# mux_chip_test_mk2.net
KiCad netlist of a schematic drawn in EAGLE
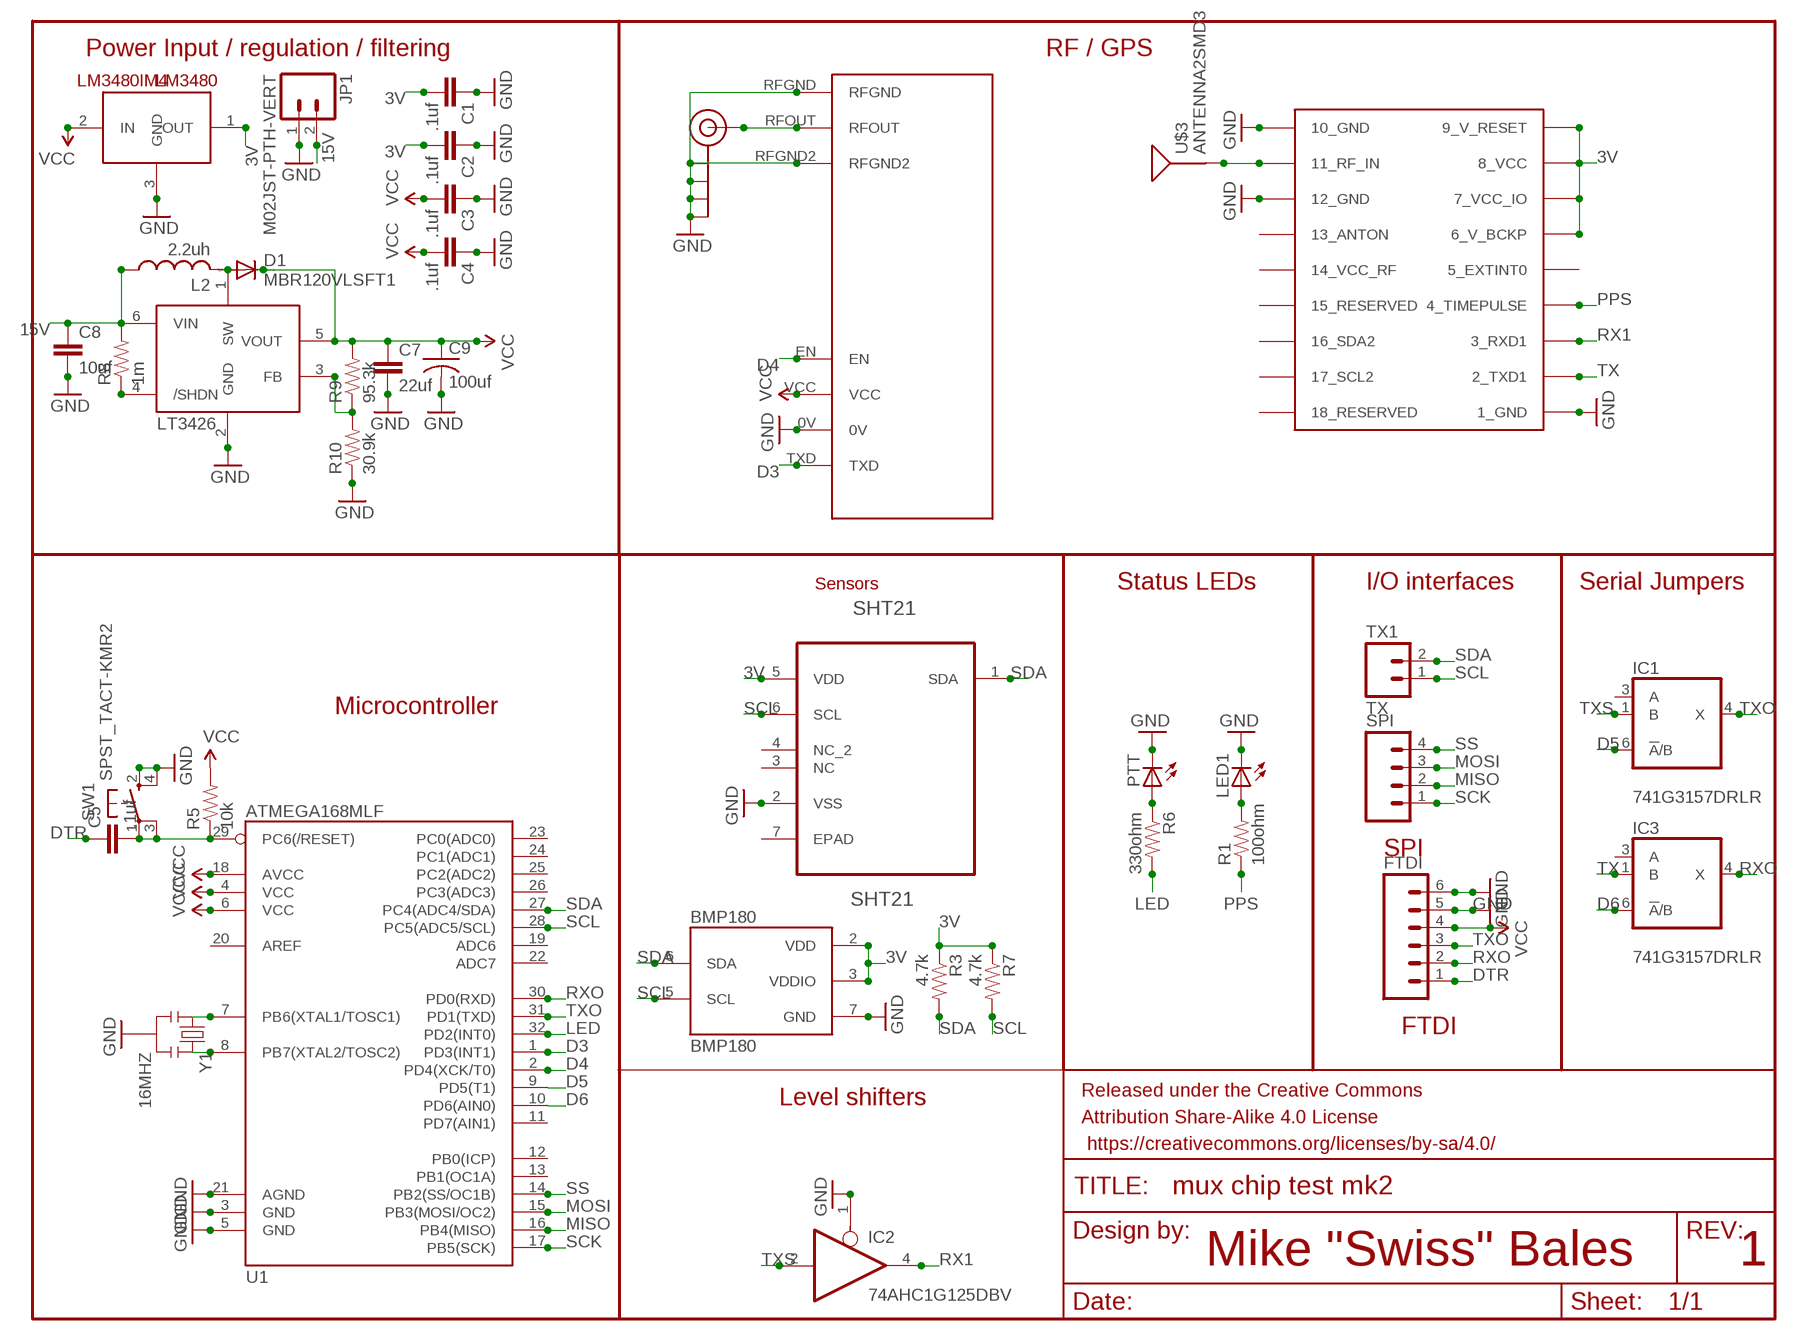
[diagram p0: schematic, sheet 1]

(export (version "E")
  (design (tool "Eeschema 10.0.6"))
  (components
    (comp (ref "BMP180")
      (value "BMP180")
      (footprint "eagle-import:BMP180")
      (libsource (lib "eagle-import") (part "BMP180"))
    )
    (comp (ref "C1")
      (value ".1uf")
      (footprint "eagle-import:0805")
      (libsource (lib "eagle-import") (part "CAP0805"))
    )
    (comp (ref "C2")
      (value ".1uf")
      (footprint "eagle-import:0805")
      (libsource (lib "eagle-import") (part "CAP0805"))
    )
    (comp (ref "C3")
      (value ".1uf")
      (footprint "eagle-import:0805")
      (libsource (lib "eagle-import") (part "CAP0805"))
    )
    (comp (ref "C4")
      (value ".1uf")
      (footprint "eagle-import:0805")
      (libsource (lib "eagle-import") (part "CAP0805"))
    )
    (comp (ref "C5")
      (value ".1uf")
      (footprint "eagle-import:0805")
      (libsource (lib "eagle-import") (part "CAP0805"))
    )
    (comp (ref "C7")
      (value "22uf")
      (footprint "eagle-import:0805")
      (libsource (lib "eagle-import") (part "CAP0805"))
    )
    (comp (ref "C8")
      (value "10uf")
      (footprint "eagle-import:0805")
      (libsource (lib "eagle-import") (part "CAP0805"))
    )
    (comp (ref "C9")
      (value "100uf")
      (footprint "eagle-import:C1206")
      (libsource (lib "eagle-import") (part "C-USC1206"))
    )
    (comp (ref "D1")
      (value "MBR120VLSFT1")
      (footprint "eagle-import:SOD123")
      (libsource (lib "eagle-import") (part "DIODE-SOD123"))
    )
    (comp (ref "FRAME1")
      (value "FRAME-LETTER")
      (footprint "eagle-import:CREATIVE_COMMONS")
      (libsource (lib "eagle-import") (part "FRAME-LETTER"))
    )
    (comp (ref "FTDI")
      (value "M06NO_SILK_FEMALE_PTH")
      (footprint "eagle-import:1X06_NO_SILK")
      (libsource (lib "eagle-import") (part "M06NO_SILK_FEMALE_PTH"))
    )
    (comp (ref "IC1")
      (value "741G3157DRLR")
      (footprint "eagle-import:DRL_R-PDSO-N6")
      (libsource (lib "eagle-import") (part "741G3157DRLR"))
    )
    (comp (ref "IC2")
      (value "74AHC1G125DBV")
      (footprint "eagle-import:SOT23-5")
      (libsource (lib "eagle-import") (part "741G125DBVAHC"))
    )
    (comp (ref "IC3")
      (value "741G3157DRLR")
      (footprint "eagle-import:DRL_R-PDSO-N6")
      (libsource (lib "eagle-import") (part "741G3157DRLR"))
    )
    (comp (ref "J$1")
      (value "SMA_EDGE")
      (footprint "eagle-import:SMA-EDGE")
      (libsource (lib "eagle-import") (part "SMA_EDGE"))
    )
    (comp (ref "JP1")
      (value "M02JST-PTH-VERT")
      (footprint "eagle-import:JST-2-PTH-VERT")
      (libsource (lib "eagle-import") (part "M02JST-PTH-VERT"))
    )
    (comp (ref "L2")
      (value "2.2uh")
      (footprint "eagle-import:L1812")
      (libsource (lib "eagle-import") (part "L-USL1812"))
    )
    (comp (ref "LED1")
      (value "LEDCHIP-LED0805")
      (footprint "eagle-import:CHIP-LED0805")
      (libsource (lib "eagle-import") (part "LEDCHIP-LED0805"))
    )
    (comp (ref "LM3480")
      (value "LM3480IM4")
      (footprint "eagle-import:SOT23-3")
      (libsource (lib "eagle-import") (part "LM3480IM4"))
    )
    (comp (ref "LT3426")
      (value "LT3426")
      (footprint "eagle-import:SOT23-6")
      (libsource (lib "eagle-import") (part "LT3426"))
    )
    (comp (ref "PTT")
      (value "LEDCHIP-LED0805")
      (footprint "eagle-import:CHIP-LED0805")
      (libsource (lib "eagle-import") (part "LEDCHIP-LED0805"))
    )
    (comp (ref "R1")
      (value "100ohm")
      (footprint "eagle-import:0805")
      (libsource (lib "eagle-import") (part "RESISTOR0805-RES"))
    )
    (comp (ref "R3")
      (value "4.7k")
      (footprint "eagle-import:0805")
      (libsource (lib "eagle-import") (part "RESISTOR0805-RES"))
    )
    (comp (ref "R5")
      (value "10k")
      (footprint "eagle-import:0805")
      (libsource (lib "eagle-import") (part "RESISTOR0805-RES"))
    )
    (comp (ref "R6")
      (value "330ohm")
      (footprint "eagle-import:0805")
      (libsource (lib "eagle-import") (part "RESISTOR0805-RES"))
    )
    (comp (ref "R7")
      (value "4.7k")
      (footprint "eagle-import:0805")
      (libsource (lib "eagle-import") (part "RESISTOR0805-RES"))
    )
    (comp (ref "R8")
      (value "1m")
      (footprint "eagle-import:0805")
      (libsource (lib "eagle-import") (part "RESISTOR0805-RES"))
    )
    (comp (ref "R9")
      (value "95.3k")
      (footprint "eagle-import:0805")
      (libsource (lib "eagle-import") (part "RESISTOR0805-RES"))
    )
    (comp (ref "R10")
      (value "30.9k")
      (footprint "eagle-import:0805")
      (libsource (lib "eagle-import") (part "RESISTOR0805-RES"))
    )
    (comp (ref "SHT21")
      (value "SHT21")
      (footprint "eagle-import:DFN300X300X110-7N")
      (libsource (lib "eagle-import") (part "SHT21"))
    )
    (comp (ref "SPI")
      (value "M04JST-PTH-VERT")
      (footprint "eagle-import:JST-4-PTH-VERT")
      (libsource (lib "eagle-import") (part "M04JST-PTH-VERT"))
    )
    (comp (ref "SW1")
      (value "SPST_TACT-KMR2")
      (footprint "eagle-import:KMR2")
      (libsource (lib "eagle-import") (part "SPST_TACT-KMR2"))
    )
    (comp (ref "TX1")
      (value "TX")
      (footprint "eagle-import:JST-2-PTH-VERT")
      (libsource (lib "eagle-import") (part "M02JST-PTH-VERT"))
    )
    (comp (ref "U$1")
      (value "UBLOX_MAX")
      (footprint "eagle-import:UBLOX_MAX")
      (libsource (lib "eagle-import") (part "UBLOX_MAX"))
    )
    (comp (ref "U$2")
      (value "RADIOMETRIX-HX1")
      (footprint "eagle-import:RADIOMETRIX-HX1")
      (libsource (lib "eagle-import") (part "RADIOMETRIX-HX1"))
    )
    (comp (ref "U$3")
      (value "ANTENNA2SMD3")
      (footprint "eagle-import:ANTENNA-CHIP4")
      (libsource (lib "eagle-import") (part "ANTENNA2SMD3"))
    )
    (comp (ref "U1")
      (value "ATMEGA168MLF")
      (footprint "eagle-import:MLF32")
      (libsource (lib "eagle-import") (part "ATMEGA168MLF"))
    )
    (comp (ref "Y1")
      (value "16MHZ")
      (footprint "eagle-import:RESONATOR-SMD")
      (libsource (lib "eagle-import") (part "RESONATOR16MHZ"))
    )
  )
  (nets
    (net (code "1") (name "/3V") (class "Default")
      (node (ref "BMP180") (pin "2") (pinfunction "VDD_2") (pintype "power_in"))
      (node (ref "BMP180") (pin "3") (pinfunction "VDDIO_3") (pintype "power_in"))
      (node (ref "C1") (pin "2") (pinfunction "2_2") (pintype "passive"))
      (node (ref "C2") (pin "2") (pinfunction "2_2") (pintype "passive"))
      (node (ref "LM3480") (pin "1") (pinfunction "OUT_1") (pintype "bidirectional"))
      (node (ref "R3") (pin "1") (pinfunction "1_1") (pintype "passive"))
      (node (ref "R7") (pin "1") (pinfunction "1_1") (pintype "passive"))
      (node (ref "SHT21") (pin "5") (pinfunction "VDD_5") (pintype "power_in"))
      (node (ref "U$1") (pin "6_V_BCKP") (pinfunction "6_V_BCKP_6_V_BCKP") (pintype "bidirectional"))
      (node (ref "U$1") (pin "7_VCC_IO") (pinfunction "7_VCC_IO_7_VCC_IO") (pintype "power_in"))
      (node (ref "U$1") (pin "8_VCC") (pinfunction "8_VCC_8_VCC") (pintype "power_in"))
      (node (ref "U$1") (pin "9_V_RESET") (pinfunction "9_V_RESET_9_V_RESET") (pintype "power_in"))
    )
    (net (code "2") (name "/15V") (class "Default")
      (node (ref "C8") (pin "1") (pinfunction "1_1") (pintype "passive"))
      (node (ref "JP1") (pin "2") (pinfunction "2_2") (pintype "passive"))
      (node (ref "L2") (pin "1") (pinfunction "1_1") (pintype "passive"))
      (node (ref "LT3426") (pin "6") (pinfunction "VIN_6") (pintype "input"))
      (node (ref "R8") (pin "2") (pinfunction "2_2") (pintype "passive"))
    )
    (net (code "3") (name "/D3") (class "Default")
      (node (ref "U$2") (pin "TXD") (pinfunction "TXD_TXD") (pintype "bidirectional"))
      (node (ref "U1") (pin "1") (pinfunction "PD3(INT1)_1") (pintype "bidirectional"))
    )
    (net (code "4") (name "/D4") (class "Default")
      (node (ref "U$2") (pin "EN") (pinfunction "EN_EN") (pintype "bidirectional"))
      (node (ref "U1") (pin "2") (pinfunction "PD4(XCK/T0)_2") (pintype "bidirectional"))
    )
    (net (code "5") (name "/D5") (class "Default")
      (node (ref "IC1") (pin "6") (pinfunction "~{A}/B_6") (pintype "input"))
      (node (ref "U1") (pin "9") (pinfunction "PD5(T1)_9") (pintype "bidirectional"))
    )
    (net (code "6") (name "/D6") (class "Default")
      (node (ref "IC3") (pin "6") (pinfunction "~{A}/B_6") (pintype "input"))
      (node (ref "U1") (pin "10") (pinfunction "PD6(AIN0)_10") (pintype "bidirectional"))
    )
    (net (code "7") (name "/DTR") (class "Default")
      (node (ref "C5") (pin "1") (pinfunction "1_1") (pintype "passive"))
      (node (ref "FTDI") (pin "1") (pinfunction "1_1") (pintype "passive"))
    )
    (net (code "8") (name "/LED") (class "Default")
      (node (ref "R6") (pin "2") (pinfunction "2_2") (pintype "passive"))
      (node (ref "U1") (pin "32") (pinfunction "PD2(INT0)_32") (pintype "bidirectional"))
    )
    (net (code "9") (name "/MISO") (class "Default")
      (node (ref "SPI") (pin "2") (pinfunction "2_2") (pintype "passive"))
      (node (ref "U1") (pin "16") (pinfunction "PB4(MISO)_16") (pintype "bidirectional"))
    )
    (net (code "10") (name "/MOSI") (class "Default")
      (node (ref "SPI") (pin "3") (pinfunction "3_3") (pintype "passive"))
      (node (ref "U1") (pin "15") (pinfunction "PB3(MOSI/OC2)_15") (pintype "bidirectional"))
    )
    (net (code "11") (name "/PPS") (class "Default")
      (node (ref "R1") (pin "1") (pinfunction "1_1") (pintype "passive"))
      (node (ref "U$1") (pin "4_TIMEPULSE") (pinfunction "4_TIMEPULSE_4_TIMEPULSE") (pintype "bidirectional"))
    )
    (net (code "12") (name "/RX1") (class "Default")
      (node (ref "IC2") (pin "4") (pinfunction "O_4") (pintype "tri_state"))
      (node (ref "U$1") (pin "3_RXD1") (pinfunction "3_RXD1_3_RXD1") (pintype "bidirectional"))
    )
    (net (code "13") (name "/RXO") (class "Default")
      (node (ref "FTDI") (pin "2") (pinfunction "2_2") (pintype "passive"))
      (node (ref "IC3") (pin "4") (pinfunction "X_4") (pintype "bidirectional"))
      (node (ref "U1") (pin "30") (pinfunction "PD0(RXD)_30") (pintype "bidirectional"))
    )
    (net (code "14") (name "/SCK") (class "Default")
      (node (ref "SPI") (pin "1") (pinfunction "1_1") (pintype "passive"))
      (node (ref "U1") (pin "17") (pinfunction "PB5(SCK)_17") (pintype "bidirectional"))
    )
    (net (code "15") (name "/SCL") (class "Default")
      (node (ref "BMP180") (pin "5") (pinfunction "SCL_5") (pintype "input"))
      (node (ref "R7") (pin "2") (pinfunction "2_2") (pintype "passive"))
      (node (ref "SHT21") (pin "6") (pinfunction "SCL_6") (pintype "input"))
      (node (ref "TX1") (pin "1") (pinfunction "1_1") (pintype "passive"))
      (node (ref "U1") (pin "28") (pinfunction "PC5(ADC5/SCL)_28") (pintype "bidirectional"))
    )
    (net (code "16") (name "/SDA") (class "Default")
      (node (ref "BMP180") (pin "6") (pinfunction "SDA_6") (pintype "bidirectional"))
      (node (ref "R3") (pin "2") (pinfunction "2_2") (pintype "passive"))
      (node (ref "SHT21") (pin "1") (pinfunction "SDA_1") (pintype "bidirectional"))
      (node (ref "TX1") (pin "2") (pinfunction "2_2") (pintype "passive"))
      (node (ref "U1") (pin "27") (pinfunction "PC4(ADC4/SDA)_27") (pintype "bidirectional"))
    )
    (net (code "17") (name "/SS") (class "Default")
      (node (ref "SPI") (pin "4") (pinfunction "4_4") (pintype "passive"))
      (node (ref "U1") (pin "14") (pinfunction "PB2(SS/OC1B)_14") (pintype "bidirectional"))
    )
    (net (code "18") (name "/TX") (class "Default")
      (node (ref "IC3") (pin "1") (pinfunction "B_1") (pintype "bidirectional"))
      (node (ref "U$1") (pin "2_TXD1") (pinfunction "2_TXD1_2_TXD1") (pintype "bidirectional"))
    )
    (net (code "19") (name "/TXO") (class "Default")
      (node (ref "FTDI") (pin "3") (pinfunction "3_3") (pintype "passive"))
      (node (ref "IC1") (pin "4") (pinfunction "X_4") (pintype "bidirectional"))
      (node (ref "U1") (pin "31") (pinfunction "PD1(TXD)_31") (pintype "bidirectional"))
    )
    (net (code "20") (name "/TXS") (class "Default")
      (node (ref "IC1") (pin "1") (pinfunction "B_1") (pintype "bidirectional"))
      (node (ref "IC2") (pin "2") (pinfunction "I_2") (pintype "input"))
    )
    (net (code "21") (name "GND") (class "Default")
      (node (ref "BMP180") (pin "7") (pinfunction "GND_7") (pintype "power_in"))
      (node (ref "C1") (pin "1") (pinfunction "1_1") (pintype "passive"))
      (node (ref "C2") (pin "1") (pinfunction "1_1") (pintype "passive"))
      (node (ref "C3") (pin "1") (pinfunction "1_1") (pintype "passive"))
      (node (ref "C4") (pin "1") (pinfunction "1_1") (pintype "passive"))
      (node (ref "C7") (pin "2") (pinfunction "2_2") (pintype "passive"))
      (node (ref "C8") (pin "2") (pinfunction "2_2") (pintype "passive"))
      (node (ref "C9") (pin "2") (pinfunction "2_2") (pintype "passive"))
      (node (ref "FTDI") (pin "5") (pinfunction "5_5") (pintype "passive"))
      (node (ref "FTDI") (pin "6") (pinfunction "6_6") (pintype "passive"))
      (node (ref "IC2") (pin "1") (pinfunction "OE_1") (pintype "input"))
      (node (ref "J$1") (pin "GND@0") (pinfunction "GND_GND@0") (pintype "bidirectional"))
      (node (ref "J$1") (pin "GND@1") (pinfunction "GND_GND@1") (pintype "bidirectional"))
      (node (ref "J$1") (pin "GND@2") (pinfunction "GND_GND@2") (pintype "bidirectional"))
      (node (ref "J$1") (pin "GND@3") (pinfunction "GND_GND@3") (pintype "bidirectional"))
      (node (ref "JP1") (pin "1") (pinfunction "1_1") (pintype "passive"))
      (node (ref "LED1") (pin "C") (pinfunction "C_C") (pintype "passive"))
      (node (ref "LM3480") (pin "3") (pinfunction "GND_3") (pintype "bidirectional"))
      (node (ref "LT3426") (pin "2") (pinfunction "GND_2") (pintype "power_in"))
      (node (ref "PTT") (pin "C") (pinfunction "C_C") (pintype "passive"))
      (node (ref "R10") (pin "1") (pinfunction "1_1") (pintype "passive"))
      (node (ref "SHT21") (pin "2") (pinfunction "VSS_2") (pintype "power_in"))
      (node (ref "SW1") (pin "2") (pinfunction "S_2") (pintype "passive"))
      (node (ref "SW1") (pin "4") (pinfunction "S1_4") (pintype "passive"))
      (node (ref "U$1") (pin "10_GND") (pinfunction "10_GND_10_GND") (pintype "power_in"))
      (node (ref "U$1") (pin "12_GND") (pinfunction "12_GND_12_GND") (pintype "power_in"))
      (node (ref "U$1") (pin "1_GND") (pinfunction "1_GND_1_GND") (pintype "power_in"))
      (node (ref "U$2") (pin "0V") (pinfunction "0V_0V") (pintype "bidirectional"))
      (node (ref "U$2") (pin "RFGND") (pinfunction "RFGND_RFGND") (pintype "bidirectional"))
      (node (ref "U$2") (pin "RFGND2") (pinfunction "RFGND2_RFGND2") (pintype "bidirectional"))
      (node (ref "U1") (pin "21") (pinfunction "AGND_21") (pintype "bidirectional"))
      (node (ref "U1") (pin "3") (pinfunction "GND_3") (pintype "bidirectional"))
      (node (ref "U1") (pin "5") (pinfunction "GND_5") (pintype "bidirectional"))
      (node (ref "Y1") (pin "2") (pinfunction "2_2") (pintype "passive"))
    )
    (net (code "22") (name "Net-(J$1-SIGNAL)") (class "Default")
      (node (ref "J$1") (pin "SIG") (pinfunction "SIGNAL_SIG") (pintype "bidirectional"))
      (node (ref "U$2") (pin "RFOUT") (pinfunction "RFOUT_RFOUT") (pintype "bidirectional"))
    )
    (net (code "23") (name "Net-(LED1-PadA)") (class "Default")
      (node (ref "LED1") (pin "A") (pinfunction "A_A") (pintype "passive"))
      (node (ref "R1") (pin "2") (pinfunction "2_2") (pintype "passive"))
    )
    (net (code "24") (name "Net-(LT3426-FB)") (class "Default")
      (node (ref "LT3426") (pin "3") (pinfunction "FB_3") (pintype "input"))
      (node (ref "R10") (pin "2") (pinfunction "2_2") (pintype "passive"))
      (node (ref "R9") (pin "1") (pinfunction "1_1") (pintype "passive"))
    )
    (net (code "25") (name "Net-(LT3426-SW)") (class "Default")
      (node (ref "D1") (pin "A") (pinfunction "A_A") (pintype "passive"))
      (node (ref "L2") (pin "2") (pinfunction "2_2") (pintype "passive"))
      (node (ref "LT3426") (pin "1") (pinfunction "SW_1") (pintype "output"))
    )
    (net (code "26") (name "Net-(LT3426-{slash}SHDN)") (class "Default")
      (node (ref "LT3426") (pin "4") (pinfunction "/SHDN_4") (pintype "input"))
      (node (ref "R8") (pin "1") (pinfunction "1_1") (pintype "passive"))
    )
    (net (code "27") (name "Net-(PTT-PadA)") (class "Default")
      (node (ref "PTT") (pin "A") (pinfunction "A_A") (pintype "passive"))
      (node (ref "R6") (pin "1") (pinfunction "1_1") (pintype "passive"))
    )
    (net (code "28") (name "Net-(SW1-P)") (class "Default")
      (node (ref "C5") (pin "2") (pinfunction "2_2") (pintype "passive"))
      (node (ref "R5") (pin "1") (pinfunction "1_1") (pintype "passive"))
      (node (ref "SW1") (pin "1") (pinfunction "P_1") (pintype "passive"))
      (node (ref "SW1") (pin "3") (pinfunction "P1_3") (pintype "passive"))
      (node (ref "U1") (pin "29") (pinfunction "PC6(/RESET)_29") (pintype "bidirectional"))
    )
    (net (code "29") (name "Net-(U$3-SIGNAL)") (class "Default")
      (node (ref "U$1") (pin "11_RF_IN") (pinfunction "11_RF_IN_11_RF_IN") (pintype "bidirectional"))
      (node (ref "U$3") (pin "SIG") (pinfunction "SIGNAL_SIG") (pintype "bidirectional"))
    )
    (net (code "30") (name "Net-(U1-PB6(XTAL1{slash}TOSC1))") (class "Default")
      (node (ref "U1") (pin "7") (pinfunction "PB6(XTAL1/TOSC1)_7") (pintype "bidirectional"))
      (node (ref "Y1") (pin "1") (pinfunction "1_1") (pintype "passive"))
    )
    (net (code "31") (name "Net-(U1-PB7(XTAL2{slash}TOSC2))") (class "Default")
      (node (ref "U1") (pin "8") (pinfunction "PB7(XTAL2/TOSC2)_8") (pintype "bidirectional"))
      (node (ref "Y1") (pin "3") (pinfunction "3_3") (pintype "passive"))
    )
    (net (code "32") (name "VCC") (class "Default")
      (node (ref "C3") (pin "2") (pinfunction "2_2") (pintype "passive"))
      (node (ref "C4") (pin "2") (pinfunction "2_2") (pintype "passive"))
      (node (ref "C7") (pin "1") (pinfunction "1_1") (pintype "passive"))
      (node (ref "C9") (pin "1") (pinfunction "1_1") (pintype "passive"))
      (node (ref "D1") (pin "C") (pinfunction "C_C") (pintype "passive"))
      (node (ref "FTDI") (pin "4") (pinfunction "4_4") (pintype "passive"))
      (node (ref "LM3480") (pin "2") (pinfunction "IN_2") (pintype "bidirectional"))
      (node (ref "LT3426") (pin "5") (pinfunction "VOUT_5") (pintype "output"))
      (node (ref "R5") (pin "2") (pinfunction "2_2") (pintype "passive"))
      (node (ref "R9") (pin "2") (pinfunction "2_2") (pintype "passive"))
      (node (ref "U$2") (pin "VCC") (pinfunction "VCC_VCC") (pintype "bidirectional"))
      (node (ref "U1") (pin "18") (pinfunction "AVCC_18") (pintype "bidirectional"))
      (node (ref "U1") (pin "4") (pinfunction "VCC_4") (pintype "bidirectional"))
      (node (ref "U1") (pin "6") (pinfunction "VCC_6") (pintype "bidirectional"))
    )
    (net (code "33") (name "unconnected-(IC1A-A-Pad3)") (class "Default")
      (node (ref "IC1") (pin "3") (pinfunction "A_3") (pintype "bidirectional"))
    )
    (net (code "34") (name "unconnected-(IC3A-A-Pad3)") (class "Default")
      (node (ref "IC3") (pin "3") (pinfunction "A_3") (pintype "bidirectional"))
    )
    (net (code "35") (name "unconnected-(SHT21-EPAD-Pad7)") (class "Default")
      (node (ref "SHT21") (pin "7") (pinfunction "EPAD_7") (pintype "passive"))
    )
    (net (code "36") (name "unconnected-(SHT21-NC-Pad3)") (class "Default")
      (node (ref "SHT21") (pin "3") (pinfunction "NC_3") (pintype "no_connect"))
    )
    (net (code "37") (name "unconnected-(SHT21-NC_2-Pad4)") (class "Default")
      (node (ref "SHT21") (pin "4") (pinfunction "NC_2_4") (pintype "no_connect"))
    )
    (net (code "38") (name "unconnected-(U$1-Pad5_EXTINT0)") (class "Default")
      (node (ref "U$1") (pin "5_EXTINT0") (pinfunction "5_EXTINT0_5_EXTINT0") (pintype "bidirectional"))
    )
    (net (code "39") (name "unconnected-(U$1-Pad13_ANTON)") (class "Default")
      (node (ref "U$1") (pin "13_ANTON") (pinfunction "13_ANTON_13_ANTON") (pintype "bidirectional"))
    )
    (net (code "40") (name "unconnected-(U$1-Pad14_VCC_RF)") (class "Default")
      (node (ref "U$1") (pin "14_VCC_RF") (pinfunction "14_VCC_RF_14_VCC_RF") (pintype "bidirectional"))
    )
    (net (code "41") (name "unconnected-(U$1-Pad15_RESERVED)") (class "Default")
      (node (ref "U$1") (pin "15_RESERVED") (pinfunction "15_RESERVED_15_RESERVED") (pintype "bidirectional"))
    )
    (net (code "42") (name "unconnected-(U$1-Pad16_SDA2)") (class "Default")
      (node (ref "U$1") (pin "16_SDA2") (pinfunction "16_SDA2_16_SDA2") (pintype "bidirectional"))
    )
    (net (code "43") (name "unconnected-(U$1-Pad17_SCL2)") (class "Default")
      (node (ref "U$1") (pin "17_SCL2") (pinfunction "17_SCL2_17_SCL2") (pintype "bidirectional"))
    )
    (net (code "44") (name "unconnected-(U$1-Pad18_RESERVED)") (class "Default")
      (node (ref "U$1") (pin "18_RESERVED") (pinfunction "18_RESERVED_18_RESERVED") (pintype "bidirectional"))
    )
    (net (code "45") (name "unconnected-(U1-ADC6-Pad19)") (class "Default")
      (node (ref "U1") (pin "19") (pinfunction "ADC6_19") (pintype "bidirectional"))
    )
    (net (code "46") (name "unconnected-(U1-ADC7-Pad22)") (class "Default")
      (node (ref "U1") (pin "22") (pinfunction "ADC7_22") (pintype "bidirectional"))
    )
    (net (code "47") (name "unconnected-(U1-AREF-Pad20)") (class "Default")
      (node (ref "U1") (pin "20") (pinfunction "AREF_20") (pintype "bidirectional"))
    )
    (net (code "48") (name "unconnected-(U1-PB0(ICP)-Pad12)") (class "Default")
      (node (ref "U1") (pin "12") (pinfunction "PB0(ICP)_12") (pintype "bidirectional"))
    )
    (net (code "49") (name "unconnected-(U1-PB1(OC1A)-Pad13)") (class "Default")
      (node (ref "U1") (pin "13") (pinfunction "PB1(OC1A)_13") (pintype "bidirectional"))
    )
    (net (code "50") (name "unconnected-(U1-PC0(ADC0)-Pad23)") (class "Default")
      (node (ref "U1") (pin "23") (pinfunction "PC0(ADC0)_23") (pintype "bidirectional"))
    )
    (net (code "51") (name "unconnected-(U1-PC1(ADC1)-Pad24)") (class "Default")
      (node (ref "U1") (pin "24") (pinfunction "PC1(ADC1)_24") (pintype "bidirectional"))
    )
    (net (code "52") (name "unconnected-(U1-PC2(ADC2)-Pad25)") (class "Default")
      (node (ref "U1") (pin "25") (pinfunction "PC2(ADC2)_25") (pintype "bidirectional"))
    )
    (net (code "53") (name "unconnected-(U1-PC3(ADC3)-Pad26)") (class "Default")
      (node (ref "U1") (pin "26") (pinfunction "PC3(ADC3)_26") (pintype "bidirectional"))
    )
    (net (code "54") (name "unconnected-(U1-PD7(AIN1)-Pad11)") (class "Default")
      (node (ref "U1") (pin "11") (pinfunction "PD7(AIN1)_11") (pintype "bidirectional"))
    )
  )
)
